# Main_PCB.net
KiCad netlist of a schematic drawn in EAGLE
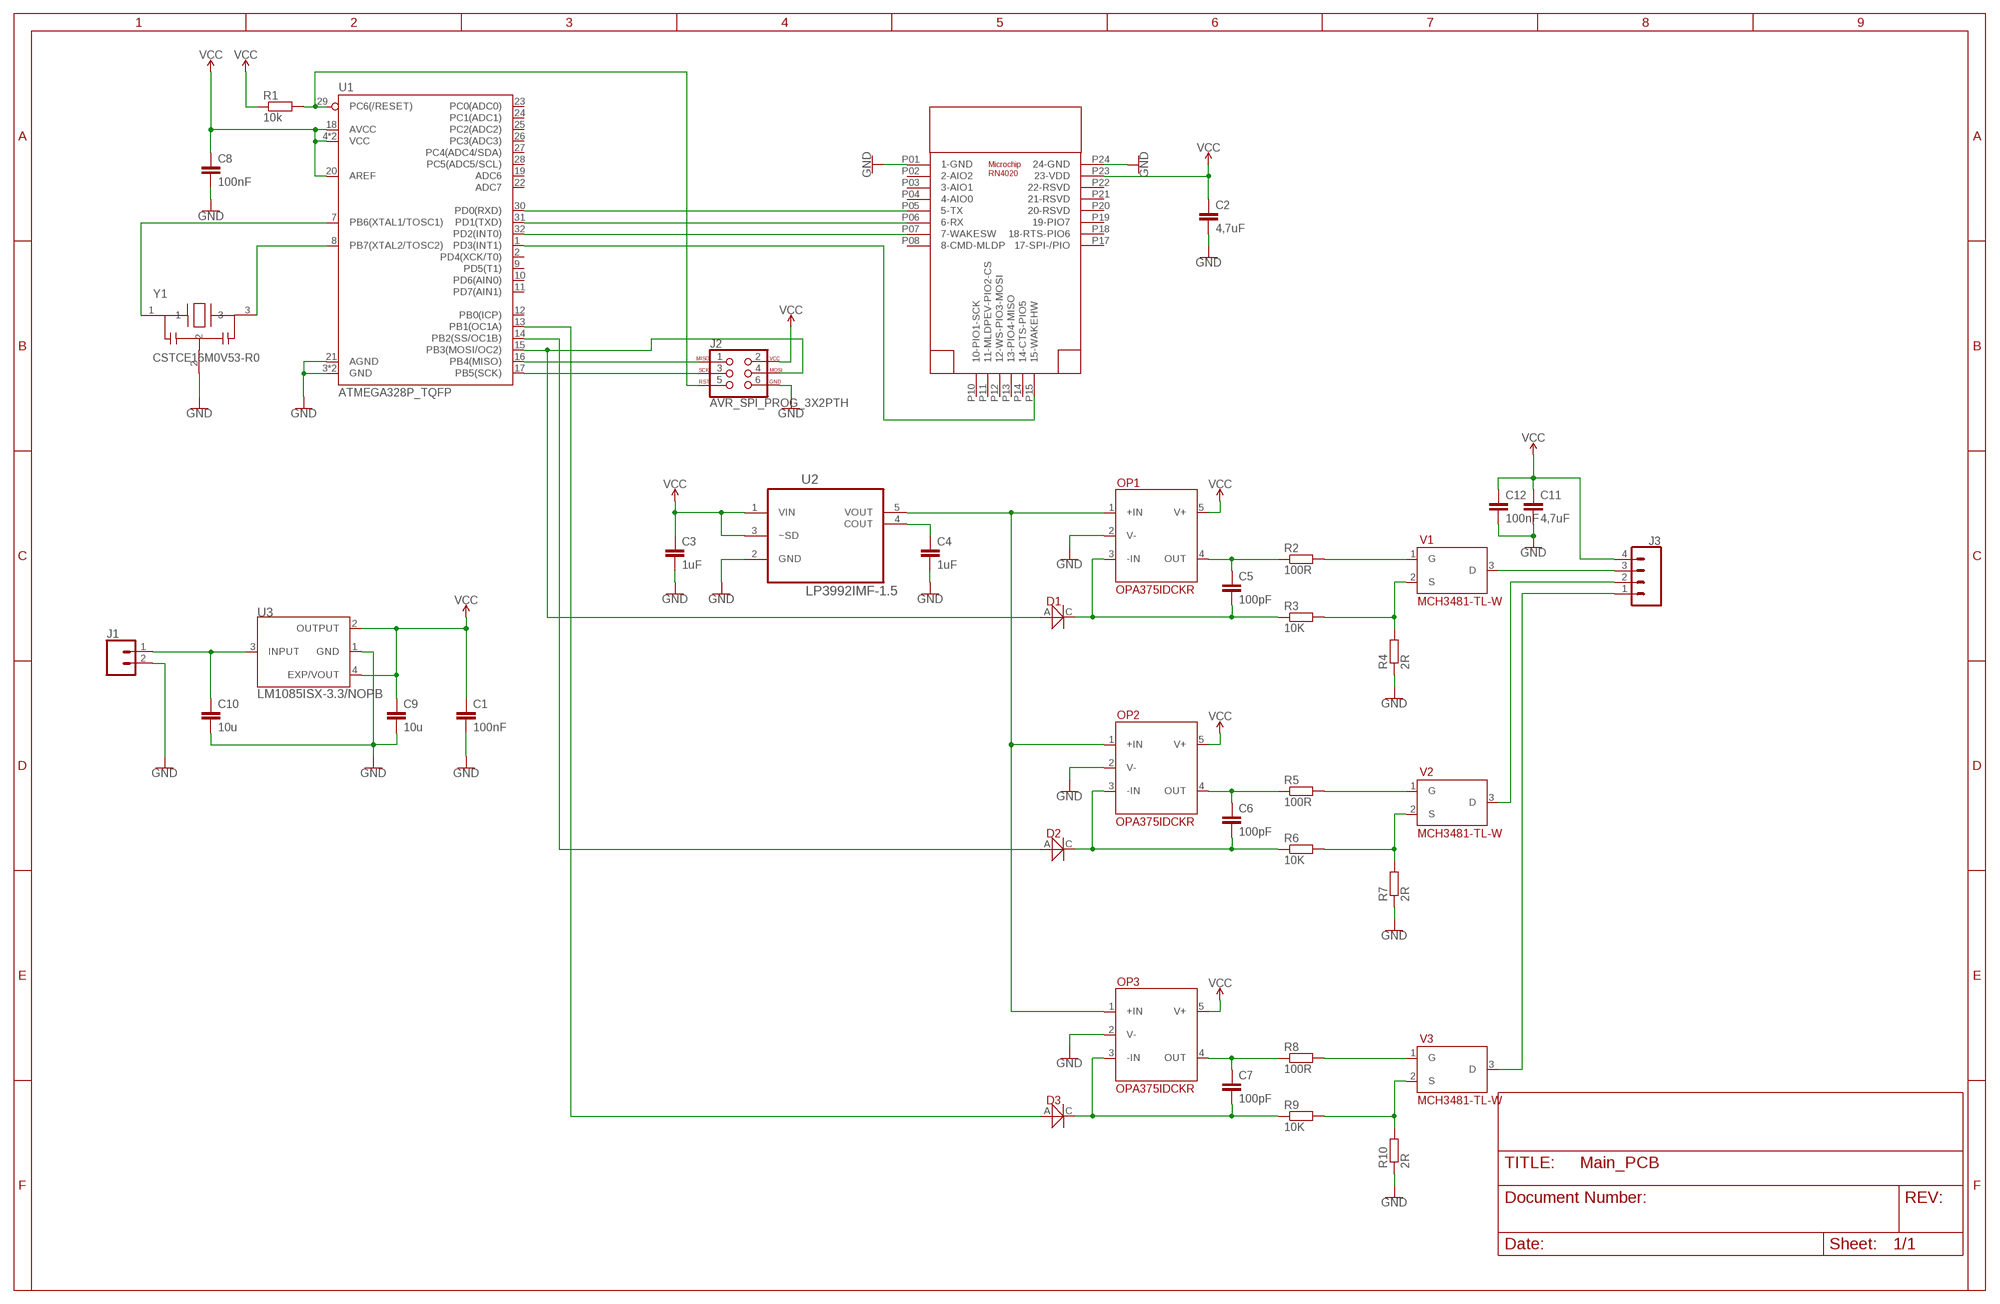
[diagram p0: schematic, sheet 1]

(export (version "E")
  (design (tool "Eeschema 10.0.6"))
  (components
    (comp (ref "C1")
      (value "100nF")
      (footprint "eagle-import:C0805K")
      (libsource (lib "eagle-import") (part "C-EUC0805K"))
    )
    (comp (ref "C2")
      (value "4,7uF")
      (footprint "eagle-import:C0805K")
      (libsource (lib "eagle-import") (part "C-EUC0805K"))
    )
    (comp (ref "C3")
      (value "1uF")
      (footprint "eagle-import:C0805K")
      (libsource (lib "eagle-import") (part "C-EUC0805K"))
    )
    (comp (ref "C4")
      (value "1uF")
      (footprint "eagle-import:C0805K")
      (libsource (lib "eagle-import") (part "C-EUC0805K"))
    )
    (comp (ref "C5")
      (value "100pF")
      (footprint "eagle-import:C0805K")
      (libsource (lib "eagle-import") (part "C-EUC0805K"))
    )
    (comp (ref "C6")
      (value "100pF")
      (footprint "eagle-import:C0805K")
      (libsource (lib "eagle-import") (part "C-EUC0805K"))
    )
    (comp (ref "C7")
      (value "100pF")
      (footprint "eagle-import:C0805K")
      (libsource (lib "eagle-import") (part "C-EUC0805K"))
    )
    (comp (ref "C8")
      (value "100nF")
      (footprint "eagle-import:C0805K")
      (libsource (lib "eagle-import") (part "C-EUC0805K"))
    )
    (comp (ref "C9")
      (value "10u")
      (footprint "eagle-import:C1206K")
      (libsource (lib "eagle-import") (part "C-EUC1206K"))
    )
    (comp (ref "C10")
      (value "10u")
      (footprint "eagle-import:C1206K")
      (libsource (lib "eagle-import") (part "C-EUC1206K"))
    )
    (comp (ref "C11")
      (value "4,7uF")
      (footprint "eagle-import:C0805K")
      (libsource (lib "eagle-import") (part "C-EUC0805K"))
    )
    (comp (ref "C12")
      (value "100nF")
      (footprint "eagle-import:C0805K")
      (libsource (lib "eagle-import") (part "C-EUC0805K"))
    )
    (comp (ref "D1")
      (value "1N4148WQ-7-F")
      (footprint "eagle-import:SOD-123")
      (libsource (lib "eagle-import") (part "1N4148WQ-7-F"))
    )
    (comp (ref "D2")
      (value "1N4148WQ-7-F")
      (footprint "eagle-import:SOD-123")
      (libsource (lib "eagle-import") (part "1N4148WQ-7-F"))
    )
    (comp (ref "D3")
      (value "1N4148WQ-7-F")
      (footprint "eagle-import:SOD-123")
      (libsource (lib "eagle-import") (part "1N4148WQ-7-F"))
    )
    (comp (ref "J1")
      (value "CONN_02-JST-2MM-SMT")
      (footprint "eagle-import:JST-2-SMD")
      (libsource (lib "eagle-import") (part "CONN_02-JST-2MM-SMT"))
    )
    (comp (ref "J2")
      (value "AVR_SPI_PROG_3X2PTH")
      (footprint "eagle-import:2X3")
      (libsource (lib "eagle-import") (part "AVR_SPI_PROG_3X2PTH"))
    )
    (comp (ref "J3")
      (value "CONN_04SMD")
      (footprint "eagle-import:1X04_SMD_RA_MALE")
      (libsource (lib "eagle-import") (part "CONN_04SMD"))
    )
    (comp (ref "OP1")
      (value "OPA375IDCKR")
      (footprint "eagle-import:SC-70-05")
      (libsource (lib "eagle-import") (part "OPA375IDCKR"))
    )
    (comp (ref "OP2")
      (value "OPA375IDCKR")
      (footprint "eagle-import:SC-70-05")
      (libsource (lib "eagle-import") (part "OPA375IDCKR"))
    )
    (comp (ref "OP3")
      (value "OPA375IDCKR")
      (footprint "eagle-import:SC-70-05")
      (libsource (lib "eagle-import") (part "OPA375IDCKR"))
    )
    (comp (ref "R1")
      (value "10k")
      (footprint "eagle-import:R0805")
      (libsource (lib "eagle-import") (part "R-EU_R0805"))
    )
    (comp (ref "R2")
      (value "100R")
      (footprint "eagle-import:R0805")
      (libsource (lib "eagle-import") (part "R-EU_R0805"))
    )
    (comp (ref "R3")
      (value "10K")
      (footprint "eagle-import:R0805")
      (libsource (lib "eagle-import") (part "R-EU_R0805"))
    )
    (comp (ref "R4")
      (value "2R")
      (footprint "eagle-import:R1210")
      (libsource (lib "eagle-import") (part "R-EU_R1210"))
    )
    (comp (ref "R5")
      (value "100R")
      (footprint "eagle-import:R0805")
      (libsource (lib "eagle-import") (part "R-EU_R0805"))
    )
    (comp (ref "R6")
      (value "10K")
      (footprint "eagle-import:R0805")
      (libsource (lib "eagle-import") (part "R-EU_R0805"))
    )
    (comp (ref "R7")
      (value "2R")
      (footprint "eagle-import:R1210")
      (libsource (lib "eagle-import") (part "R-EU_R1210"))
    )
    (comp (ref "R8")
      (value "100R")
      (footprint "eagle-import:R0805")
      (libsource (lib "eagle-import") (part "R-EU_R0805"))
    )
    (comp (ref "R9")
      (value "10K")
      (footprint "eagle-import:R0805")
      (libsource (lib "eagle-import") (part "R-EU_R0805"))
    )
    (comp (ref "R10")
      (value "2R")
      (footprint "eagle-import:R1210")
      (libsource (lib "eagle-import") (part "R-EU_R1210"))
    )
    (comp (ref "U$1")
      (value "RN4020")
      (footprint "eagle-import:RN4020SMD")
      (libsource (lib "eagle-import") (part "RN4020"))
    )
    (comp (ref "U1")
      (value "ATMEGA328P_TQFP")
      (footprint "eagle-import:TQFP32-08")
      (libsource (lib "eagle-import") (part "ATMEGA328P_TQFP"))
    )
    (comp (ref "U2")
      (value "LP3992IMF-1.5")
      (footprint "eagle-import:SOT95P284X122-5N")
      (fields (field (name "MF") "Texas Instruments"))
      (libsource (lib "eagle-import") (part "LP3992IMF-1.5"))
    )
    (comp (ref "U3")
      (value "LM1085ISX-3.3/NOPB")
      (footprint "eagle-import:DPAK254P1435X464-4N")
      (fields
        (field (name "DIGI-KEY_PART_NUMBER") "LM1085ISX-3.3/NOPBCT-ND")
        (field (name "MF") "Texas Instruments")
      )
      (libsource (lib "eagle-import") (part "LM1085ISX-3.3/NOPB"))
    )
    (comp (ref "V1")
      (value "MCH3481-TL-W")
      (footprint "eagle-import:SC-70FL")
      (libsource (lib "eagle-import") (part "MCH3481-TL-W"))
    )
    (comp (ref "V2")
      (value "MCH3481-TL-W")
      (footprint "eagle-import:SC-70FL")
      (libsource (lib "eagle-import") (part "MCH3481-TL-W"))
    )
    (comp (ref "V3")
      (value "MCH3481-TL-W")
      (footprint "eagle-import:SC-70FL")
      (libsource (lib "eagle-import") (part "MCH3481-TL-W"))
    )
    (comp (ref "Y1")
      (value "CSTCE16M0V53-R0")
      (footprint "eagle-import:OSC_CSTCE16M0V53-R0")
      (fields (field (name "DIGI-KEY_PART_NUMBER") "490-1198-1-ND") (field (name "MF") "Murata"))
      (libsource (lib "eagle-import") (part "CSTCE16M0V53-R0"))
    )
  )
  (nets
    (net (code "1") (name "GND") (class "Default")
      (node (ref "C1") (pin "2") (pinfunction "2_2") (pintype "passive"))
      (node (ref "C10") (pin "2") (pinfunction "2_2") (pintype "passive"))
      (node (ref "C11") (pin "2") (pinfunction "2_2") (pintype "passive"))
      (node (ref "C12") (pin "2") (pinfunction "2_2") (pintype "passive"))
      (node (ref "C2") (pin "2") (pinfunction "2_2") (pintype "passive"))
      (node (ref "C3") (pin "2") (pinfunction "2_2") (pintype "passive"))
      (node (ref "C4") (pin "2") (pinfunction "2_2") (pintype "passive"))
      (node (ref "C8") (pin "2") (pinfunction "2_2") (pintype "passive"))
      (node (ref "C9") (pin "2") (pinfunction "2_2") (pintype "passive"))
      (node (ref "J1") (pin "2") (pinfunction "1_2") (pintype "passive"))
      (node (ref "J2") (pin "6") (pinfunction "6_6") (pintype "passive"))
      (node (ref "OP1") (pin "2") (pinfunction "V-_2") (pintype "power_in"))
      (node (ref "OP2") (pin "2") (pinfunction "V-_2") (pintype "power_in"))
      (node (ref "OP3") (pin "2") (pinfunction "V-_2") (pintype "power_in"))
      (node (ref "R10") (pin "1") (pinfunction "1_1") (pintype "passive"))
      (node (ref "R4") (pin "1") (pinfunction "1_1") (pintype "passive"))
      (node (ref "R7") (pin "1") (pinfunction "1_1") (pintype "passive"))
      (node (ref "U$1") (pin "P01") (pinfunction "1-GND_P01") (pintype "bidirectional"))
      (node (ref "U$1") (pin "P24") (pinfunction "24-GND_P24") (pintype "bidirectional"))
      (node (ref "U1") (pin "21") (pinfunction "AGND_21") (pintype "bidirectional"))
      (node (ref "U1") (pin "3") (pinfunction "GND_3") (pintype "bidirectional"))
      (node (ref "U1") (pin "5") (pinfunction "GND_5") (pintype "bidirectional"))
      (node (ref "U2") (pin "2") (pinfunction "GND_2") (pintype "passive"))
      (node (ref "U3") (pin "1") (pinfunction "GND_1") (pintype "power_in"))
      (node (ref "Y1") (pin "2") (pinfunction "2_2") (pintype "passive"))
    )
    (net (code "2") (name "Net-(D1-ANODE)") (class "Default")
      (node (ref "D1") (pin "A") (pinfunction "ANODE_A") (pintype "input"))
      (node (ref "J2") (pin "4") (pinfunction "4_4") (pintype "passive"))
      (node (ref "U1") (pin "15") (pinfunction "PB3(MOSI/OC2)_15") (pintype "bidirectional"))
    )
    (net (code "3") (name "Net-(D1-CATHODE)") (class "Default")
      (node (ref "C5") (pin "2") (pinfunction "2_2") (pintype "passive"))
      (node (ref "D1") (pin "C") (pinfunction "CATHODE_C") (pintype "output"))
      (node (ref "OP1") (pin "3") (pinfunction "-IN_3") (pintype "input"))
      (node (ref "R3") (pin "1") (pinfunction "1_1") (pintype "passive"))
    )
    (net (code "4") (name "Net-(D2-ANODE)") (class "Default")
      (node (ref "D2") (pin "A") (pinfunction "ANODE_A") (pintype "input"))
      (node (ref "U1") (pin "14") (pinfunction "PB2(SS/OC1B)_14") (pintype "bidirectional"))
    )
    (net (code "5") (name "Net-(D2-CATHODE)") (class "Default")
      (node (ref "C6") (pin "2") (pinfunction "2_2") (pintype "passive"))
      (node (ref "D2") (pin "C") (pinfunction "CATHODE_C") (pintype "output"))
      (node (ref "OP2") (pin "3") (pinfunction "-IN_3") (pintype "input"))
      (node (ref "R6") (pin "1") (pinfunction "1_1") (pintype "passive"))
    )
    (net (code "6") (name "Net-(D3-ANODE)") (class "Default")
      (node (ref "D3") (pin "A") (pinfunction "ANODE_A") (pintype "input"))
      (node (ref "U1") (pin "13") (pinfunction "PB1(OC1A)_13") (pintype "bidirectional"))
    )
    (net (code "7") (name "Net-(D3-CATHODE)") (class "Default")
      (node (ref "C7") (pin "2") (pinfunction "2_2") (pintype "passive"))
      (node (ref "D3") (pin "C") (pinfunction "CATHODE_C") (pintype "output"))
      (node (ref "OP3") (pin "3") (pinfunction "-IN_3") (pintype "input"))
      (node (ref "R9") (pin "1") (pinfunction "1_1") (pintype "passive"))
    )
    (net (code "8") (name "Net-(J1-2)") (class "Default")
      (node (ref "C10") (pin "1") (pinfunction "1_1") (pintype "passive"))
      (node (ref "J1") (pin "1") (pinfunction "2_1") (pintype "passive"))
      (node (ref "U3") (pin "3") (pinfunction "INPUT_3") (pintype "input"))
    )
    (net (code "9") (name "Net-(OP1-+IN)") (class "Default")
      (node (ref "OP1") (pin "1") (pinfunction "+IN_1") (pintype "input"))
      (node (ref "OP2") (pin "1") (pinfunction "+IN_1") (pintype "input"))
      (node (ref "OP3") (pin "1") (pinfunction "+IN_1") (pintype "input"))
      (node (ref "U2") (pin "5") (pinfunction "VOUT_5") (pintype "output"))
    )
    (net (code "10") (name "Net-(OP1-OUT)") (class "Default")
      (node (ref "C5") (pin "1") (pinfunction "1_1") (pintype "passive"))
      (node (ref "OP1") (pin "4") (pinfunction "OUT_4") (pintype "output"))
      (node (ref "R2") (pin "1") (pinfunction "1_1") (pintype "passive"))
    )
    (net (code "11") (name "Net-(OP2-OUT)") (class "Default")
      (node (ref "C6") (pin "1") (pinfunction "1_1") (pintype "passive"))
      (node (ref "OP2") (pin "4") (pinfunction "OUT_4") (pintype "output"))
      (node (ref "R5") (pin "1") (pinfunction "1_1") (pintype "passive"))
    )
    (net (code "12") (name "Net-(OP3-OUT)") (class "Default")
      (node (ref "C7") (pin "1") (pinfunction "1_1") (pintype "passive"))
      (node (ref "OP3") (pin "4") (pinfunction "OUT_4") (pintype "output"))
      (node (ref "R8") (pin "1") (pinfunction "1_1") (pintype "passive"))
    )
    (net (code "13") (name "Net-(U$1-5-TX)") (class "Default")
      (node (ref "U$1") (pin "P05") (pinfunction "5-TX_P05") (pintype "bidirectional"))
      (node (ref "U1") (pin "30") (pinfunction "PD0(RXD)_30") (pintype "bidirectional"))
    )
    (net (code "14") (name "Net-(U$1-6-RX)") (class "Default")
      (node (ref "U$1") (pin "P06") (pinfunction "6-RX_P06") (pintype "bidirectional"))
      (node (ref "U1") (pin "31") (pinfunction "PD1(TXD)_31") (pintype "bidirectional"))
    )
    (net (code "15") (name "Net-(U$1-7-WAKESW)") (class "Default")
      (node (ref "U$1") (pin "P07") (pinfunction "7-WAKESW_P07") (pintype "bidirectional"))
      (node (ref "U1") (pin "32") (pinfunction "PD2(INT0)_32") (pintype "bidirectional"))
    )
    (net (code "16") (name "Net-(U$1-15-WAKEHW)") (class "Default")
      (node (ref "U$1") (pin "P15") (pinfunction "15-WAKEHW_P15") (pintype "bidirectional"))
      (node (ref "U1") (pin "1") (pinfunction "PD3(INT1)_1") (pintype "bidirectional"))
    )
    (net (code "17") (name "Net-(U1-PB4(MISO))") (class "Default")
      (node (ref "J2") (pin "1") (pinfunction "1_1") (pintype "passive"))
      (node (ref "U1") (pin "16") (pinfunction "PB4(MISO)_16") (pintype "bidirectional"))
    )
    (net (code "18") (name "Net-(U1-PB5(SCK))") (class "Default")
      (node (ref "J2") (pin "3") (pinfunction "3_3") (pintype "passive"))
      (node (ref "U1") (pin "17") (pinfunction "PB5(SCK)_17") (pintype "bidirectional"))
    )
    (net (code "19") (name "Net-(U1-PB6(XTAL1{slash}TOSC1))") (class "Default")
      (node (ref "U1") (pin "7") (pinfunction "PB6(XTAL1/TOSC1)_7") (pintype "bidirectional"))
      (node (ref "Y1") (pin "1") (pinfunction "1_1") (pintype "input"))
    )
    (net (code "20") (name "Net-(U1-PB7(XTAL2{slash}TOSC2))") (class "Default")
      (node (ref "U1") (pin "8") (pinfunction "PB7(XTAL2/TOSC2)_8") (pintype "bidirectional"))
      (node (ref "Y1") (pin "3") (pinfunction "3_3") (pintype "output"))
    )
    (net (code "21") (name "Net-(U1-PC6({slash}RESET))") (class "Default")
      (node (ref "J2") (pin "5") (pinfunction "5_5") (pintype "passive"))
      (node (ref "R1") (pin "2") (pinfunction "2_2") (pintype "passive"))
      (node (ref "U1") (pin "29") (pinfunction "PC6(/RESET)_29") (pintype "bidirectional"))
    )
    (net (code "22") (name "Net-(U2-COUT)") (class "Default")
      (node (ref "C4") (pin "1") (pinfunction "1_1") (pintype "passive"))
      (node (ref "U2") (pin "4") (pinfunction "COUT_4") (pintype "output"))
    )
    (net (code "23") (name "Net-(V1-D)") (class "Default")
      (node (ref "J3") (pin "3") (pinfunction "3_3") (pintype "passive"))
      (node (ref "V1") (pin "3") (pinfunction "D_3") (pintype "input"))
    )
    (net (code "24") (name "Net-(V1-G)") (class "Default")
      (node (ref "R2") (pin "2") (pinfunction "2_2") (pintype "passive"))
      (node (ref "V1") (pin "1") (pinfunction "G_1") (pintype "input"))
    )
    (net (code "25") (name "Net-(V1-S)") (class "Default")
      (node (ref "R3") (pin "2") (pinfunction "2_2") (pintype "passive"))
      (node (ref "R4") (pin "2") (pinfunction "2_2") (pintype "passive"))
      (node (ref "V1") (pin "2") (pinfunction "S_2") (pintype "output"))
    )
    (net (code "26") (name "Net-(V2-D)") (class "Default")
      (node (ref "J3") (pin "2") (pinfunction "2_2") (pintype "passive"))
      (node (ref "V2") (pin "3") (pinfunction "D_3") (pintype "input"))
    )
    (net (code "27") (name "Net-(V2-G)") (class "Default")
      (node (ref "R5") (pin "2") (pinfunction "2_2") (pintype "passive"))
      (node (ref "V2") (pin "1") (pinfunction "G_1") (pintype "input"))
    )
    (net (code "28") (name "Net-(V2-S)") (class "Default")
      (node (ref "R6") (pin "2") (pinfunction "2_2") (pintype "passive"))
      (node (ref "R7") (pin "2") (pinfunction "2_2") (pintype "passive"))
      (node (ref "V2") (pin "2") (pinfunction "S_2") (pintype "output"))
    )
    (net (code "29") (name "Net-(V3-D)") (class "Default")
      (node (ref "J3") (pin "1") (pinfunction "1_1") (pintype "passive"))
      (node (ref "V3") (pin "3") (pinfunction "D_3") (pintype "input"))
    )
    (net (code "30") (name "Net-(V3-G)") (class "Default")
      (node (ref "R8") (pin "2") (pinfunction "2_2") (pintype "passive"))
      (node (ref "V3") (pin "1") (pinfunction "G_1") (pintype "input"))
    )
    (net (code "31") (name "Net-(V3-S)") (class "Default")
      (node (ref "R10") (pin "2") (pinfunction "2_2") (pintype "passive"))
      (node (ref "R9") (pin "2") (pinfunction "2_2") (pintype "passive"))
      (node (ref "V3") (pin "2") (pinfunction "S_2") (pintype "output"))
    )
    (net (code "32") (name "VCC") (class "Default")
      (node (ref "C1") (pin "1") (pinfunction "1_1") (pintype "passive"))
      (node (ref "C11") (pin "1") (pinfunction "1_1") (pintype "passive"))
      (node (ref "C12") (pin "1") (pinfunction "1_1") (pintype "passive"))
      (node (ref "C2") (pin "1") (pinfunction "1_1") (pintype "passive"))
      (node (ref "C3") (pin "1") (pinfunction "1_1") (pintype "passive"))
      (node (ref "C8") (pin "1") (pinfunction "1_1") (pintype "passive"))
      (node (ref "C9") (pin "1") (pinfunction "1_1") (pintype "passive"))
      (node (ref "J2") (pin "2") (pinfunction "2_2") (pintype "passive"))
      (node (ref "J3") (pin "4") (pinfunction "4_4") (pintype "passive"))
      (node (ref "OP1") (pin "5") (pinfunction "V+_5") (pintype "power_in"))
      (node (ref "OP2") (pin "5") (pinfunction "V+_5") (pintype "power_in"))
      (node (ref "OP3") (pin "5") (pinfunction "V+_5") (pintype "power_in"))
      (node (ref "R1") (pin "1") (pinfunction "1_1") (pintype "passive"))
      (node (ref "U$1") (pin "P23") (pinfunction "23-VDD_P23") (pintype "bidirectional"))
      (node (ref "U1") (pin "18") (pinfunction "AVCC_18") (pintype "bidirectional"))
      (node (ref "U1") (pin "20") (pinfunction "AREF_20") (pintype "bidirectional"))
      (node (ref "U1") (pin "4") (pinfunction "VCC_4") (pintype "bidirectional"))
      (node (ref "U1") (pin "6") (pinfunction "VCC_6") (pintype "bidirectional"))
      (node (ref "U2") (pin "1") (pinfunction "VIN_1") (pintype "power_in"))
      (node (ref "U2") (pin "3") (pinfunction "~{SD}_3") (pintype "input"))
      (node (ref "U3") (pin "2") (pinfunction "OUTPUT_2") (pintype "output"))
      (node (ref "U3") (pin "4") (pinfunction "EXP/VOUT_4") (pintype "power_in"))
    )
    (net (code "33") (name "unconnected-(U$1-2-AIO2-PadP02)") (class "Default")
      (node (ref "U$1") (pin "P02") (pinfunction "2-AIO2_P02") (pintype "bidirectional"))
    )
    (net (code "34") (name "unconnected-(U$1-3-AIO1-PadP03)") (class "Default")
      (node (ref "U$1") (pin "P03") (pinfunction "3-AIO1_P03") (pintype "bidirectional"))
    )
    (net (code "35") (name "unconnected-(U$1-4-AIO0-PadP04)") (class "Default")
      (node (ref "U$1") (pin "P04") (pinfunction "4-AIO0_P04") (pintype "bidirectional"))
    )
    (net (code "36") (name "unconnected-(U$1-8-CMD-MLDP-PadP08)") (class "Default")
      (node (ref "U$1") (pin "P08") (pinfunction "8-CMD-MLDP_P08") (pintype "bidirectional"))
    )
    (net (code "37") (name "unconnected-(U$1-10-PIO1-SCK-PadP10)") (class "Default")
      (node (ref "U$1") (pin "P10") (pinfunction "10-PIO1-SCK_P10") (pintype "bidirectional"))
    )
    (net (code "38") (name "unconnected-(U$1-11-MLDPEV-PIO2-CS-PadP11)") (class "Default")
      (node (ref "U$1") (pin "P11") (pinfunction "11-MLDPEV-PIO2-CS_P11") (pintype "bidirectional"))
    )
    (net (code "39") (name "unconnected-(U$1-12-WS-PIO3-MOSI-PadP12)") (class "Default")
      (node (ref "U$1") (pin "P12") (pinfunction "12-WS-PIO3-MOSI_P12") (pintype "bidirectional"))
    )
    (net (code "40") (name "unconnected-(U$1-13-PIO4-MISO-PadP13)") (class "Default")
      (node (ref "U$1") (pin "P13") (pinfunction "13-PIO4-MISO_P13") (pintype "bidirectional"))
    )
    (net (code "41") (name "unconnected-(U$1-14-CTS-PIO5-PadP14)") (class "Default")
      (node (ref "U$1") (pin "P14") (pinfunction "14-CTS-PIO5_P14") (pintype "bidirectional"))
    )
    (net (code "42") (name "unconnected-(U$1-17-SPI-{slash}PIO-PadP17)") (class "Default")
      (node (ref "U$1") (pin "P17") (pinfunction "17-SPI-/PIO_P17") (pintype "bidirectional"))
    )
    (net (code "43") (name "unconnected-(U$1-18-RTS-PIO6-PadP18)") (class "Default")
      (node (ref "U$1") (pin "P18") (pinfunction "18-RTS-PIO6_P18") (pintype "bidirectional"))
    )
    (net (code "44") (name "unconnected-(U$1-19-PIO7-PadP19)") (class "Default")
      (node (ref "U$1") (pin "P19") (pinfunction "19-PIO7_P19") (pintype "bidirectional"))
    )
    (net (code "45") (name "unconnected-(U$1-20-RSVD-PadP20)") (class "Default")
      (node (ref "U$1") (pin "P20") (pinfunction "20-RSVD_P20") (pintype "bidirectional"))
    )
    (net (code "46") (name "unconnected-(U$1-21-RSVD-PadP21)") (class "Default")
      (node (ref "U$1") (pin "P21") (pinfunction "21-RSVD_P21") (pintype "bidirectional"))
    )
    (net (code "47") (name "unconnected-(U$1-22-RSVD-PadP22)") (class "Default")
      (node (ref "U$1") (pin "P22") (pinfunction "22-RSVD_P22") (pintype "bidirectional"))
    )
    (net (code "48") (name "unconnected-(U1-ADC6-Pad19)") (class "Default")
      (node (ref "U1") (pin "19") (pinfunction "ADC6_19") (pintype "bidirectional"))
    )
    (net (code "49") (name "unconnected-(U1-ADC7-Pad22)") (class "Default")
      (node (ref "U1") (pin "22") (pinfunction "ADC7_22") (pintype "bidirectional"))
    )
    (net (code "50") (name "unconnected-(U1-PB0(ICP)-Pad12)") (class "Default")
      (node (ref "U1") (pin "12") (pinfunction "PB0(ICP)_12") (pintype "bidirectional"))
    )
    (net (code "51") (name "unconnected-(U1-PC0(ADC0)-Pad23)") (class "Default")
      (node (ref "U1") (pin "23") (pinfunction "PC0(ADC0)_23") (pintype "bidirectional"))
    )
    (net (code "52") (name "unconnected-(U1-PC1(ADC1)-Pad24)") (class "Default")
      (node (ref "U1") (pin "24") (pinfunction "PC1(ADC1)_24") (pintype "bidirectional"))
    )
    (net (code "53") (name "unconnected-(U1-PC2(ADC2)-Pad25)") (class "Default")
      (node (ref "U1") (pin "25") (pinfunction "PC2(ADC2)_25") (pintype "bidirectional"))
    )
    (net (code "54") (name "unconnected-(U1-PC3(ADC3)-Pad26)") (class "Default")
      (node (ref "U1") (pin "26") (pinfunction "PC3(ADC3)_26") (pintype "bidirectional"))
    )
    (net (code "55") (name "unconnected-(U1-PC4(ADC4{slash}SDA)-Pad27)") (class "Default")
      (node (ref "U1") (pin "27") (pinfunction "PC4(ADC4/SDA)_27") (pintype "bidirectional"))
    )
    (net (code "56") (name "unconnected-(U1-PC5(ADC5{slash}SCL)-Pad28)") (class "Default")
      (node (ref "U1") (pin "28") (pinfunction "PC5(ADC5/SCL)_28") (pintype "bidirectional"))
    )
    (net (code "57") (name "unconnected-(U1-PD4(XCK{slash}T0)-Pad2)") (class "Default")
      (node (ref "U1") (pin "2") (pinfunction "PD4(XCK/T0)_2") (pintype "bidirectional"))
    )
    (net (code "58") (name "unconnected-(U1-PD5(T1)-Pad9)") (class "Default")
      (node (ref "U1") (pin "9") (pinfunction "PD5(T1)_9") (pintype "bidirectional"))
    )
    (net (code "59") (name "unconnected-(U1-PD6(AIN0)-Pad10)") (class "Default")
      (node (ref "U1") (pin "10") (pinfunction "PD6(AIN0)_10") (pintype "bidirectional"))
    )
    (net (code "60") (name "unconnected-(U1-PD7(AIN1)-Pad11)") (class "Default")
      (node (ref "U1") (pin "11") (pinfunction "PD7(AIN1)_11") (pintype "bidirectional"))
    )
  )
)
